# Databus.net
KiCad netlist of a schematic drawn in Altium Designer
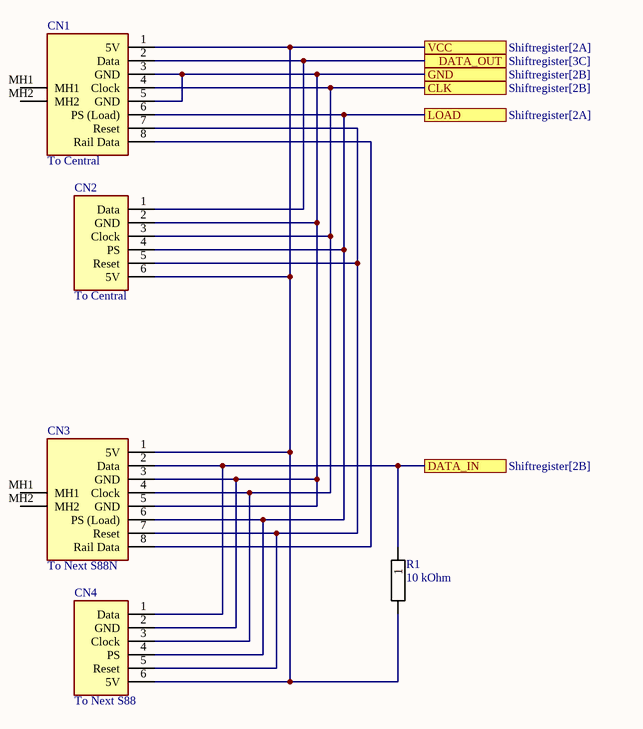
[diagram p0: Databus.SchDoc]

(export (version "E")
  (design (tool "Eeschema 10.0.6"))
  (components
    (comp (ref "CN1")
      (value "To Central")
      (footprint "RJ45_Connector")
      (description "Connector")
      (fields
        (field (name "MANUFACTURER_PART_NUMBER") "2562910000")
        (field (name "MOUSER PART NUMBER") "470-2562910000")
      )
      (libsource (lib "Schematic_Library_S88N") (part "RJ45_Connector"))
    )
    (comp (ref "CN2")
      (value "To Central")
      (footprint "6 pin header")
      (description "78511-406")
      (fields (field (name "MOUSER PART NUMBER") "649-78511-406"))
      (libsource (lib "Schematic_Library_S88N") (part "6 pin header"))
    )
    (comp (ref "CN3")
      (value "To Next S88N")
      (footprint "RJ45_Connector")
      (description "Connector")
      (fields
        (field (name "MANUFACTURER_PART_NUMBER") "2562910000")
        (field (name "MOUSER PART NUMBER") "470-2562910000")
      )
      (libsource (lib "Schematic_Library_S88N") (part "RJ45_Connector"))
    )
    (comp (ref "CN4")
      (value "To Next S88")
      (footprint "6 pin header")
      (description "78511-406")
      (fields (field (name "MOUSER PART NUMBER") "649-78511-406"))
      (libsource (lib "Schematic_Library_S88N") (part "6 pin header"))
    )
    (comp (ref "R1")
      (value "10 kOhm")
      (footprint "1N4007")
      (fields (field (name "TOLERANCE") "5%"))
      (libsource (lib "Schematic_Library_S88N") (part "Resistor"))
    )
  )
  (nets
    (net (code "1") (name "/CLK") (class "Default")
      (node (ref "CN1") (pin "4") (pinfunction "Clock_4") (pintype "passive"))
      (node (ref "CN2") (pin "3") (pinfunction "Clock_3") (pintype "passive"))
      (node (ref "CN3") (pin "4") (pinfunction "Clock_4") (pintype "passive"))
      (node (ref "CN4") (pin "3") (pinfunction "Clock_3") (pintype "passive"))
    )
    (net (code "2") (name "/DATA_IN") (class "Default")
      (node (ref "CN3") (pin "2") (pinfunction "Data_2") (pintype "passive"))
      (node (ref "CN4") (pin "1") (pinfunction "Data_1") (pintype "passive"))
      (node (ref "R1") (pin "1") (pinfunction "1_1") (pintype "passive"))
    )
    (net (code "3") (name "/DATA_OUT") (class "Default")
      (node (ref "CN1") (pin "2") (pinfunction "Data_2") (pintype "passive"))
      (node (ref "CN2") (pin "1") (pinfunction "Data_1") (pintype "passive"))
    )
    (net (code "4") (name "/GND") (class "Default")
      (node (ref "CN1") (pin "3") (pinfunction "GND_3") (pintype "passive"))
      (node (ref "CN1") (pin "5") (pinfunction "GND_5") (pintype "passive"))
      (node (ref "CN2") (pin "2") (pinfunction "GND_2") (pintype "passive"))
      (node (ref "CN3") (pin "3") (pinfunction "GND_3") (pintype "passive"))
      (node (ref "CN3") (pin "5") (pinfunction "GND_5") (pintype "passive"))
      (node (ref "CN4") (pin "2") (pinfunction "GND_2") (pintype "passive"))
    )
    (net (code "5") (name "/LOAD") (class "Default")
      (node (ref "CN1") (pin "6") (pinfunction "PS_(Load)_6") (pintype "passive"))
      (node (ref "CN2") (pin "4") (pinfunction "PS_4") (pintype "passive"))
      (node (ref "CN3") (pin "6") (pinfunction "PS_(Load)_6") (pintype "passive"))
      (node (ref "CN4") (pin "4") (pinfunction "PS_4") (pintype "passive"))
    )
    (net (code "6") (name "/VCC") (class "Default")
      (node (ref "CN1") (pin "1") (pinfunction "5V_1") (pintype "passive"))
      (node (ref "CN2") (pin "6") (pinfunction "5V_6") (pintype "passive"))
      (node (ref "CN3") (pin "1") (pinfunction "5V_1") (pintype "passive"))
      (node (ref "CN4") (pin "6") (pinfunction "5V_6") (pintype "passive"))
      (node (ref "R1") (pin "2") (pinfunction "2_2") (pintype "passive"))
    )
    (net (code "7") (name "Net-(CN1-Rail_Data)") (class "Default")
      (node (ref "CN1") (pin "8") (pinfunction "Rail_Data_8") (pintype "passive"))
      (node (ref "CN3") (pin "8") (pinfunction "Rail_Data_8") (pintype "passive"))
    )
    (net (code "8") (name "Net-(CN1-Reset)") (class "Default")
      (node (ref "CN1") (pin "7") (pinfunction "Reset_7") (pintype "passive"))
      (node (ref "CN2") (pin "5") (pinfunction "Reset_5") (pintype "passive"))
      (node (ref "CN3") (pin "7") (pinfunction "Reset_7") (pintype "passive"))
      (node (ref "CN4") (pin "5") (pinfunction "Reset_5") (pintype "passive"))
    )
    (net (code "9") (name "unconnected-(CN1-PadMH1)") (class "Default")
      (node (ref "CN1") (pin "MH1") (pinfunction "MH1_MH1") (pintype "passive"))
    )
    (net (code "10") (name "unconnected-(CN1-PadMH2)") (class "Default")
      (node (ref "CN1") (pin "MH2") (pinfunction "MH2_MH2") (pintype "passive"))
    )
    (net (code "11") (name "unconnected-(CN3-PadMH1)") (class "Default")
      (node (ref "CN3") (pin "MH1") (pinfunction "MH1_MH1") (pintype "passive"))
    )
    (net (code "12") (name "unconnected-(CN3-PadMH2)") (class "Default")
      (node (ref "CN3") (pin "MH2") (pinfunction "MH2_MH2") (pintype "passive"))
    )
  )
)
